# slouchpad_v1_rightpad.net
KiCad netlist of a schematic drawn in EAGLE
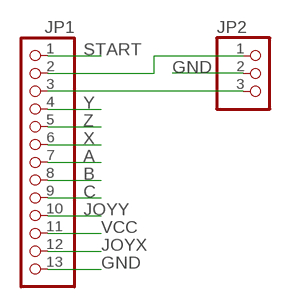
[diagram p0: schematic, sheet 1]
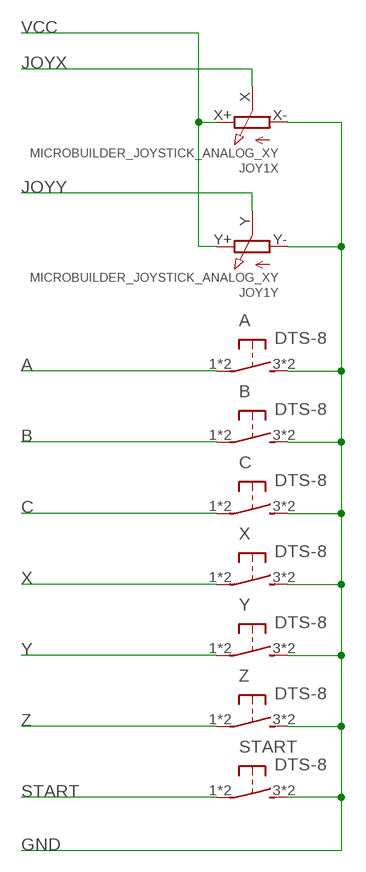
[diagram p1: schematic, sheet 2]

(export (version "E")
  (design (tool "Eeschema 10.0.6"))
  (components
    (comp (ref "JP1")
      (value "PINHD-1X13")
      (footprint "eagle-import:1X13")
      (libsource (lib "eagle-import") (part "PINHD-1X13"))
    )
    (comp (ref "JP2")
      (value "PINHD-1X3")
      (footprint "eagle-import:1X03")
      (libsource (lib "eagle-import") (part "PINHD-1X3"))
    )
    (comp (ref "A")
      (value "DTS-8")
      (footprint "eagle-import:DTS-8")
      (libsource (lib "eagle-import") (part "DTS-8"))
    )
    (comp (ref "B")
      (value "DTS-8")
      (footprint "eagle-import:DTS-8")
      (libsource (lib "eagle-import") (part "DTS-8"))
    )
    (comp (ref "C")
      (value "DTS-8")
      (footprint "eagle-import:DTS-8")
      (libsource (lib "eagle-import") (part "DTS-8"))
    )
    (comp (ref "JOY1")
      (value "MICROBUILDER_JOYSTICK_ANALOG_XY")
      (footprint "eagle-import:MICROBUILDER_JOYSTICK_ANALOG_MINITHM")
      (libsource (lib "eagle-import") (part "MICROBUILDER_JOYSTICK_ANALOG_XY"))
    )
    (comp (ref "START")
      (value "DTS-8")
      (footprint "eagle-import:DTS-8")
      (libsource (lib "eagle-import") (part "DTS-8"))
    )
    (comp (ref "X")
      (value "DTS-8")
      (footprint "eagle-import:DTS-8")
      (libsource (lib "eagle-import") (part "DTS-8"))
    )
    (comp (ref "Y")
      (value "DTS-8")
      (footprint "eagle-import:DTS-8")
      (libsource (lib "eagle-import") (part "DTS-8"))
    )
    (comp (ref "Z")
      (value "DTS-8")
      (footprint "eagle-import:DTS-8")
      (libsource (lib "eagle-import") (part "DTS-8"))
    )
  )
  (nets
    (net (code "1") (name "A") (class "Default")
      (node (ref "A") (pin "1") (pinfunction "1_1") (pintype "passive"))
      (node (ref "A") (pin "2") (pinfunction "1_2") (pintype "passive"))
      (node (ref "JP1") (pin "7") (pinfunction "7_7") (pintype "passive"))
    )
    (net (code "2") (name "B") (class "Default")
      (node (ref "B") (pin "1") (pinfunction "1_1") (pintype "passive"))
      (node (ref "B") (pin "2") (pinfunction "1_2") (pintype "passive"))
      (node (ref "JP1") (pin "8") (pinfunction "8_8") (pintype "passive"))
    )
    (net (code "3") (name "C") (class "Default")
      (node (ref "C") (pin "1") (pinfunction "1_1") (pintype "passive"))
      (node (ref "C") (pin "2") (pinfunction "1_2") (pintype "passive"))
      (node (ref "JP1") (pin "9") (pinfunction "9_9") (pintype "passive"))
    )
    (net (code "4") (name "GND") (class "Default")
      (node (ref "A") (pin "3") (pinfunction "2_3") (pintype "passive"))
      (node (ref "A") (pin "4") (pinfunction "2_4") (pintype "passive"))
      (node (ref "B") (pin "3") (pinfunction "2_3") (pintype "passive"))
      (node (ref "B") (pin "4") (pinfunction "2_4") (pintype "passive"))
      (node (ref "C") (pin "3") (pinfunction "2_3") (pintype "passive"))
      (node (ref "C") (pin "4") (pinfunction "2_4") (pintype "passive"))
      (node (ref "JOY1") (pin "X-") (pinfunction "A_X-") (pintype "passive"))
      (node (ref "JOY1") (pin "Y-") (pinfunction "A_Y-") (pintype "passive"))
      (node (ref "JP1") (pin "13") (pinfunction "13_13") (pintype "passive"))
      (node (ref "JP2") (pin "2") (pinfunction "2_2") (pintype "passive"))
      (node (ref "START") (pin "3") (pinfunction "2_3") (pintype "passive"))
      (node (ref "START") (pin "4") (pinfunction "2_4") (pintype "passive"))
      (node (ref "X") (pin "3") (pinfunction "2_3") (pintype "passive"))
      (node (ref "X") (pin "4") (pinfunction "2_4") (pintype "passive"))
      (node (ref "Y") (pin "3") (pinfunction "2_3") (pintype "passive"))
      (node (ref "Y") (pin "4") (pinfunction "2_4") (pintype "passive"))
      (node (ref "Z") (pin "3") (pinfunction "2_3") (pintype "passive"))
      (node (ref "Z") (pin "4") (pinfunction "2_4") (pintype "passive"))
    )
    (net (code "5") (name "JOYX") (class "Default")
      (node (ref "JOY1") (pin "X") (pinfunction "S_X") (pintype "passive"))
      (node (ref "JP1") (pin "12") (pinfunction "12_12") (pintype "passive"))
    )
    (net (code "6") (name "JOYY") (class "Default")
      (node (ref "JOY1") (pin "Y") (pinfunction "S_Y") (pintype "passive"))
      (node (ref "JP1") (pin "10") (pinfunction "10_10") (pintype "passive"))
    )
    (net (code "7") (name "Net-(JP1-Pad2)") (class "Default")
      (node (ref "JP1") (pin "2") (pinfunction "2_2") (pintype "passive"))
      (node (ref "JP2") (pin "1") (pinfunction "1_1") (pintype "passive"))
    )
    (net (code "8") (name "Net-(JP1-Pad3)") (class "Default")
      (node (ref "JP1") (pin "3") (pinfunction "3_3") (pintype "passive"))
      (node (ref "JP2") (pin "3") (pinfunction "3_3") (pintype "passive"))
    )
    (net (code "9") (name "START") (class "Default")
      (node (ref "JP1") (pin "1") (pinfunction "1_1") (pintype "passive"))
      (node (ref "START") (pin "1") (pinfunction "1_1") (pintype "passive"))
      (node (ref "START") (pin "2") (pinfunction "1_2") (pintype "passive"))
    )
    (net (code "10") (name "VCC") (class "Default")
      (node (ref "JOY1") (pin "X+") (pinfunction "E_X+") (pintype "passive"))
      (node (ref "JOY1") (pin "Y+") (pinfunction "E_Y+") (pintype "passive"))
      (node (ref "JP1") (pin "11") (pinfunction "11_11") (pintype "passive"))
    )
    (net (code "11") (name "X") (class "Default")
      (node (ref "JP1") (pin "6") (pinfunction "6_6") (pintype "passive"))
      (node (ref "X") (pin "1") (pinfunction "1_1") (pintype "passive"))
      (node (ref "X") (pin "2") (pinfunction "1_2") (pintype "passive"))
    )
    (net (code "12") (name "Y") (class "Default")
      (node (ref "JP1") (pin "4") (pinfunction "4_4") (pintype "passive"))
      (node (ref "Y") (pin "1") (pinfunction "1_1") (pintype "passive"))
      (node (ref "Y") (pin "2") (pinfunction "1_2") (pintype "passive"))
    )
    (net (code "13") (name "Z") (class "Default")
      (node (ref "JP1") (pin "5") (pinfunction "5_5") (pintype "passive"))
      (node (ref "Z") (pin "1") (pinfunction "1_1") (pintype "passive"))
      (node (ref "Z") (pin "2") (pinfunction "1_2") (pintype "passive"))
    )
  )
)
